# dcdc_5v0_3v3.net
KiCad netlist of a schematic drawn in Altium Designer
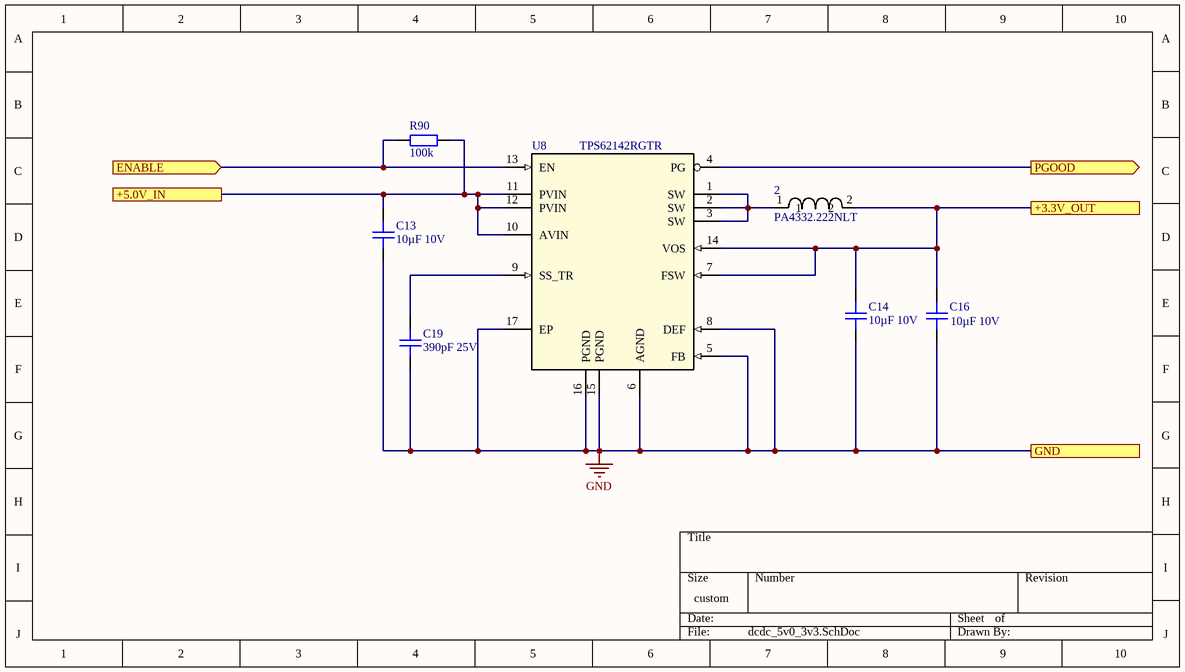
[diagram p0: dcdc_5v0_3v3.SchDoc]

(export (version "E")
  (design (tool "Eeschema 10.0.6"))
  (components
    (comp (ref "2")
      (value "PA4332.222NLT")
      (footprint "PA4332")
      (description "Imported")
      (libsource (lib "ti-import") (part "PA4332.222NLT"))
    )
    (comp (ref "C13")
      (value "10µF 10V")
      (footprint "0805C")
      (description "Ceramic, 10µF, ±10%, 10V, X7R, –55 to 125°C, 0805 (2012),RoHS, Automotive")
      (fields (field (name "PART NUMBER") "GCJ21BR71A106KE01") (field (name "TOLERANCE") "±10%"))
      (libsource (lib "master-010106") (part "gen_C_ceramic_10u_10V_X7R_0805"))
    )
    (comp (ref "C14")
      (value "10µF 10V")
      (footprint "0805C")
      (description "Ceramic, 10µF, ±10%, 10V, X7R, –55 to 125°C, 0805 (2012),RoHS, Automotive")
      (fields (field (name "PART NUMBER") "GCJ21BR71A106KE01") (field (name "TOLERANCE") "±10%"))
      (libsource (lib "master-010106") (part "gen_C_ceramic_10u_10V_X7R_0805"))
    )
    (comp (ref "C16")
      (value "10µF 10V")
      (footprint "0805C")
      (description "Ceramic, 10µF, ±10%, 10V, X7R, –55 to 125°C, 0805 (2012),RoHS, Automotive")
      (fields (field (name "PART NUMBER") "GCJ21BR71A106KE01") (field (name "TOLERANCE") "±10%"))
      (libsource (lib "master-010106") (part "gen_C_ceramic_10u_10V_X7R_0805"))
    )
    (comp (ref "C19")
      (value "390pF 25V")
      (footprint "0402C")
      (description "Ceramic, 390pF, ±5%, 25V, C0G, 25 to 125°C, 0402 (1005),RoHS, Automotive")
      (fields (field (name "PART NUMBER") "GCM1555C1H180JA16#") (field (name "TOLERANCE") "±5%"))
      (libsource (lib "master-010106") (part "gen_C_ceramic_390p_25V_C0G_0402"))
    )
    (comp (ref "R90")
      (value "100k")
      (footprint "0603R")
      (description "SMD Resistor 100k 0603")
      (fields (field (name "PART NUMBER") "gen_R_100k_0603"))
      (libsource (lib "master-010106") (part "gen_R_100k_0603"))
    )
    (comp (ref "U8")
      (value "TPS62142RGTR")
      (footprint "RGT0016C")
      (description "Imported")
      (fields (field (name "MANUFACTURER") "Texas Instruments"))
      (libsource (lib "ti-import") (part "TPS62142RGTR"))
    )
  )
  (nets
    (net (code "1") (name "/+3.3V_OUT") (class "Default")
      (node (ref "2") (pin "2") (pinfunction "2_2") (pintype "passive"))
      (node (ref "C14") (pin "1") (pinfunction "1_1") (pintype "passive"))
      (node (ref "C16") (pin "1") (pinfunction "1_1") (pintype "passive"))
      (node (ref "U8") (pin "14") (pinfunction "VOS_14") (pintype "input"))
      (node (ref "U8") (pin "7") (pinfunction "FSW_7") (pintype "input"))
    )
    (net (code "2") (name "/+5.0V_IN") (class "Default")
      (node (ref "C13") (pin "1") (pinfunction "1_1") (pintype "passive"))
      (node (ref "R90") (pin "1") (pinfunction "1_1") (pintype "passive"))
      (node (ref "U8") (pin "10") (pinfunction "AVIN_10") (pintype "power_in"))
      (node (ref "U8") (pin "11") (pinfunction "PVIN_11") (pintype "power_in"))
      (node (ref "U8") (pin "12") (pinfunction "PVIN_12") (pintype "power_in"))
    )
    (net (code "3") (name "/ENABLE") (class "Default")
      (node (ref "R90") (pin "2") (pinfunction "2_2") (pintype "passive"))
      (node (ref "U8") (pin "13") (pinfunction "EN_13") (pintype "input"))
    )
    (net (code "4") (name "/PGOOD") (class "Default")
      (node (ref "U8") (pin "4") (pinfunction "PG_4") (pintype "open_collector"))
    )
    (net (code "5") (name "GND") (class "Default")
      (node (ref "C13") (pin "2") (pinfunction "2_2") (pintype "passive"))
      (node (ref "C14") (pin "2") (pinfunction "2_2") (pintype "passive"))
      (node (ref "C16") (pin "2") (pinfunction "2_2") (pintype "passive"))
      (node (ref "C19") (pin "1") (pinfunction "1_1") (pintype "passive"))
      (node (ref "U8") (pin "15") (pinfunction "PGND_15") (pintype "power_in"))
      (node (ref "U8") (pin "16") (pinfunction "PGND_16") (pintype "power_in"))
      (node (ref "U8") (pin "17") (pinfunction "EP_17") (pintype "power_in"))
      (node (ref "U8") (pin "5") (pinfunction "FB_5") (pintype "input"))
      (node (ref "U8") (pin "6") (pinfunction "AGND_6") (pintype "power_in"))
      (node (ref "U8") (pin "8") (pinfunction "DEF_8") (pintype "input"))
    )
    (net (code "6") (name "Net-(2-Pad1)") (class "Default")
      (node (ref "2") (pin "1") (pinfunction "1_1") (pintype "passive"))
      (node (ref "U8") (pin "1") (pinfunction "SW_1") (pintype "power_in"))
      (node (ref "U8") (pin "2") (pinfunction "SW_2") (pintype "power_in"))
      (node (ref "U8") (pin "3") (pinfunction "SW_3") (pintype "power_in"))
    )
    (net (code "7") (name "Net-(U8-SS_TR)") (class "Default")
      (node (ref "C19") (pin "2") (pinfunction "2_2") (pintype "passive"))
      (node (ref "U8") (pin "9") (pinfunction "SS_TR_9") (pintype "input"))
    )
  )
)
